# SensorIoTDisplay.net
KiCad netlist of a schematic drawn in EAGLE
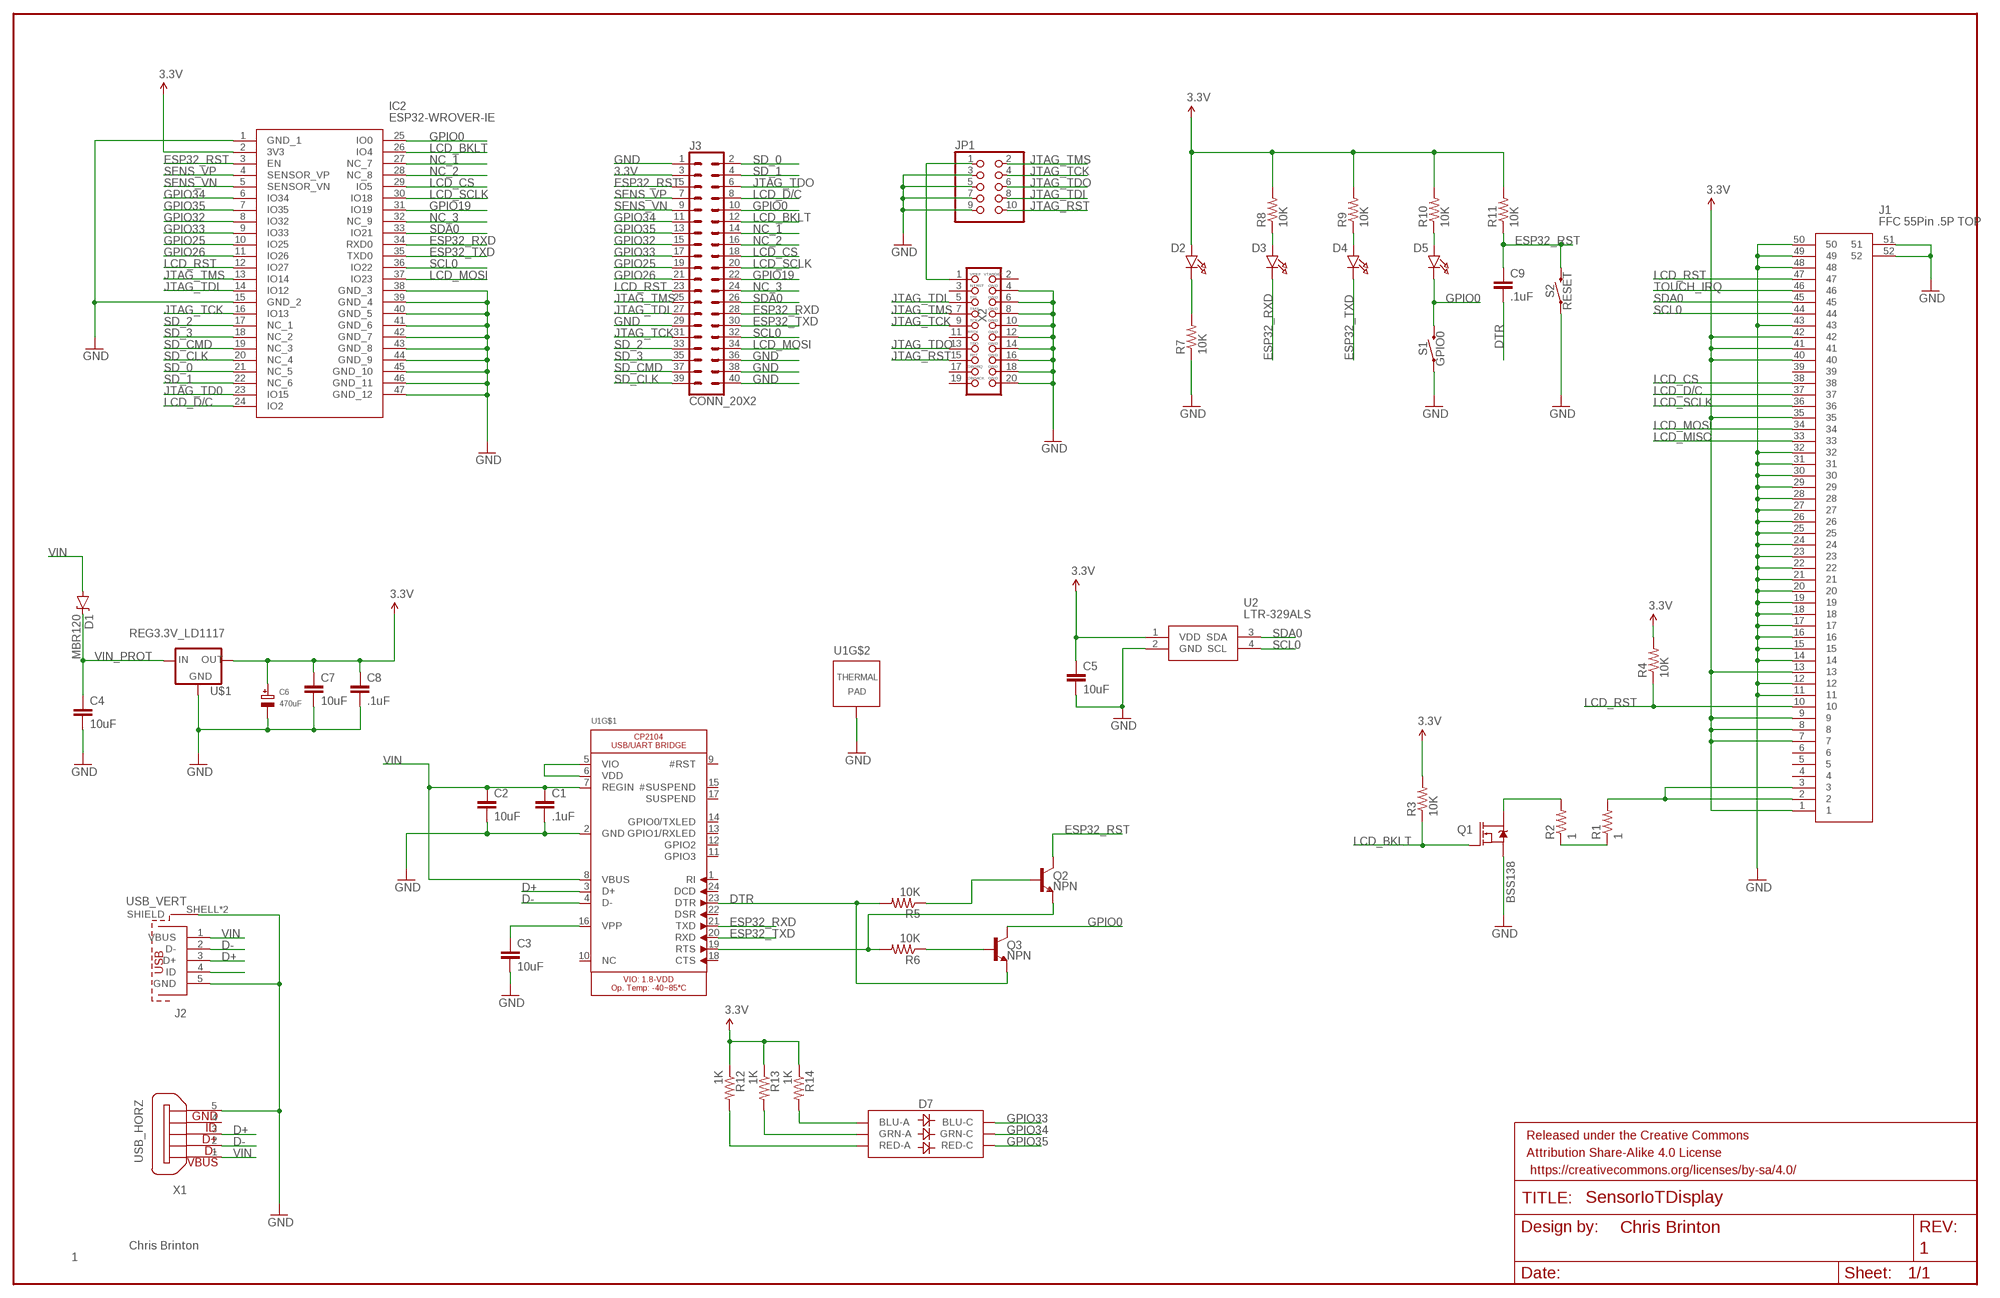
[diagram p0: schematic, sheet 1]

(export (version "E")
  (design (tool "Eeschema 10.0.6"))
  (components
    (comp (ref "C1")
      (value ".1uF")
      (footprint "eagle-import:0805")
      (libsource (lib "eagle-import") (part "CAP0805"))
    )
    (comp (ref "C2")
      (value "10uF")
      (footprint "eagle-import:0805")
      (libsource (lib "eagle-import") (part "CAP0805"))
    )
    (comp (ref "C3")
      (value "10uF")
      (footprint "eagle-import:0805")
      (libsource (lib "eagle-import") (part "CAP0805"))
    )
    (comp (ref "C4")
      (value "10uF")
      (footprint "eagle-import:0805")
      (libsource (lib "eagle-import") (part "CAP0805"))
    )
    (comp (ref "C5")
      (value "10uF")
      (footprint "eagle-import:0805")
      (libsource (lib "eagle-import") (part "CAP0805"))
    )
    (comp (ref "C6")
      (value "470uF")
      (footprint "eagle-import:EIA7343-31_D-R")
      (libsource (lib "eagle-import") (part "CAP_TANTALUMD/7343_REFLOW"))
    )
    (comp (ref "C7")
      (value "10uF")
      (footprint "eagle-import:0805")
      (libsource (lib "eagle-import") (part "CAP0805"))
    )
    (comp (ref "C8")
      (value ".1uF")
      (footprint "eagle-import:0805")
      (libsource (lib "eagle-import") (part "CAP0805"))
    )
    (comp (ref "C9")
      (value ".1uF")
      (footprint "eagle-import:0805")
      (libsource (lib "eagle-import") (part "CAP0805"))
    )
    (comp (ref "D1")
      (value "MBR120")
      (footprint "eagle-import:SOD-123")
      (libsource (lib "eagle-import") (part "DIODE-ZENER16V"))
    )
    (comp (ref "D2")
      (value "RED")
      (footprint "eagle-import:CHIPLED_0805_NOOUTLINE")
      (libsource (lib "eagle-import") (part "LED0805_NOOUTLINE"))
    )
    (comp (ref "D3")
      (value "GREEN")
      (footprint "eagle-import:CHIPLED_0805_NOOUTLINE")
      (libsource (lib "eagle-import") (part "LED0805_NOOUTLINE"))
    )
    (comp (ref "D4")
      (value "BLUE")
      (footprint "eagle-import:CHIPLED_0805_NOOUTLINE")
      (libsource (lib "eagle-import") (part "LED0805_NOOUTLINE"))
    )
    (comp (ref "D5")
      (value "BLUE")
      (footprint "eagle-import:CHIPLED_0805_NOOUTLINE")
      (libsource (lib "eagle-import") (part "LED0805_NOOUTLINE"))
    )
    (comp (ref "D7")
      (value "LED-RGBNO_IC")
      (footprint "eagle-import:LED-TRICOLOR-5050")
      (libsource (lib "eagle-import") (part "LED-RGBNO_IC"))
    )
    (comp (ref "FRAME1")
      (value "FRAME-LEDGER")
      (footprint "eagle-import:CREATIVE_COMMONS")
      (fields (field (name "DESIGNER") "Chris Brinton") (field (name "REV") "1"))
      (libsource (lib "eagle-import") (part "FRAME-LEDGER"))
    )
    (comp (ref "IC2")
      (value "ESP32-WROVER-IE")
      (footprint "eagle-import:ESP32WROVERIEM213EH6464UH3Q0")
      (fields
        (field (name "MANUFACTURER_PART_NUMBER") "ESP32-WROVER-IE(M213EH6464UH3Q0)")
        (field (name "MOUSER_PART_NUMBER") "356-ESP32WRVIE6464UC")
      )
      (libsource (lib "eagle-import") (part "ESP32-WROVER-IE_M213EH6464UH3Q"))
    )
    (comp (ref "J1")
      (value "FFC 55Pin .5P TOP")
      (footprint "eagle-import:FH12A50S05SH55")
      (fields
        (field (name "MANUFACTURER_PART_NUMBER") "FH12A-50S-0.5SH(55)")
        (field (name "MOUSER_PART_NUMBER") "798-FH12A-50S0.5SH55")
        (field (name "RS_PART_NUMBER") "6882833P")
      )
      (libsource (lib "eagle-import") (part "FH12A-50S-0.5SH_55_"))
    )
    (comp (ref "J2")
      (value "USB_VERT")
      (footprint "eagle-import:614105150621")
      (fields (field (name "MF") "Wurth Electronics") (field (name "MP") "614105150621"))
      (libsource (lib "eagle-import") (part "614105150621"))
    )
    (comp (ref "J3")
      (value "CONN_20X2")
      (footprint "eagle-import:2X20")
      (libsource (lib "eagle-import") (part "CONN_20X2"))
    )
    (comp (ref "JP1")
      (value "HEADER-2X51.27MM")
      (footprint "eagle-import:2X05_1.27MM_SMT")
      (libsource (lib "eagle-import") (part "HEADER-2X51.27MM"))
    )
    (comp (ref "Q1")
      (value "BSS138")
      (footprint "eagle-import:SOT23-3")
      (libsource (lib "eagle-import") (part "MOSFET-NCH-BSS138"))
    )
    (comp (ref "Q2")
      (value "NPN")
      (footprint "eagle-import:SOT23-3")
      (libsource (lib "eagle-import") (part "TRANS_NPN-MMBT2222AL"))
    )
    (comp (ref "Q3")
      (value "NPN")
      (footprint "eagle-import:SOT23-3")
      (libsource (lib "eagle-import") (part "TRANS_NPN-MMBT2222AL"))
    )
    (comp (ref "R1")
      (value "1")
      (footprint "eagle-import:0805")
      (libsource (lib "eagle-import") (part "RESISTOR0805-RES"))
    )
    (comp (ref "R2")
      (value "1")
      (footprint "eagle-import:0805")
      (libsource (lib "eagle-import") (part "RESISTOR0805-RES"))
    )
    (comp (ref "R3")
      (value "10K")
      (footprint "eagle-import:0805")
      (libsource (lib "eagle-import") (part "RESISTOR0805-RES"))
    )
    (comp (ref "R4")
      (value "10K")
      (footprint "eagle-import:0805")
      (libsource (lib "eagle-import") (part "RESISTOR0805-RES"))
    )
    (comp (ref "R5")
      (value "10K")
      (footprint "eagle-import:0805")
      (libsource (lib "eagle-import") (part "RESISTOR0805-RES"))
    )
    (comp (ref "R6")
      (value "10K")
      (footprint "eagle-import:0805")
      (libsource (lib "eagle-import") (part "RESISTOR0805-RES"))
    )
    (comp (ref "R7")
      (value "10K")
      (footprint "eagle-import:0805")
      (libsource (lib "eagle-import") (part "RESISTOR0805-RES"))
    )
    (comp (ref "R8")
      (value "10K")
      (footprint "eagle-import:0805")
      (libsource (lib "eagle-import") (part "RESISTOR0805-RES"))
    )
    (comp (ref "R9")
      (value "10K")
      (footprint "eagle-import:0805")
      (libsource (lib "eagle-import") (part "RESISTOR0805-RES"))
    )
    (comp (ref "R10")
      (value "10K")
      (footprint "eagle-import:0805")
      (libsource (lib "eagle-import") (part "RESISTOR0805-RES"))
    )
    (comp (ref "R11")
      (value "10K")
      (footprint "eagle-import:0805")
      (libsource (lib "eagle-import") (part "RESISTOR0805-RES"))
    )
    (comp (ref "R12")
      (value "1K")
      (footprint "eagle-import:0805")
      (libsource (lib "eagle-import") (part "RESISTOR0805-RES"))
    )
    (comp (ref "R13")
      (value "1K")
      (footprint "eagle-import:0805")
      (libsource (lib "eagle-import") (part "RESISTOR0805-RES"))
    )
    (comp (ref "R14")
      (value "1K")
      (footprint "eagle-import:0805")
      (libsource (lib "eagle-import") (part "RESISTOR0805-RES"))
    )
    (comp (ref "S1")
      (value "GPIO0")
      (footprint "eagle-import:TACTILE_SWITCH_SMD_4.6X2.8MM")
      (libsource (lib "eagle-import") (part "MOMENTARY-SWITCH-SPST-SMD-4.6X2.8MM"))
    )
    (comp (ref "S2")
      (value "RESET")
      (footprint "eagle-import:TACTILE_SWITCH_SMD_4.6X2.8MM")
      (libsource (lib "eagle-import") (part "MOMENTARY-SWITCH-SPST-SMD-4.6X2.8MM"))
    )
    (comp (ref "U$1")
      (value "REG3.3V_LD1117")
      (footprint "eagle-import:SOT223")
      (libsource (lib "eagle-import") (part "V_REG_LD1117VXXLD1117-SMD"))
    )
    (comp (ref "U1")
      (value "CP2104")
      (footprint "eagle-import:QFN24_4MM_SMSC")
      (libsource (lib "eagle-import") (part "CP2104"))
    )
    (comp (ref "U2")
      (value "LTR-329ALS")
      (footprint "eagle-import:LTR329ALS01")
      (fields
        (field (name "MANUFACTURER_PART_NUMBER") "LTR-329ALS-01")
        (field (name "MOUSER_PART_NUMBER") "859-LTR-329ALS-01")
      )
      (libsource (lib "eagle-import") (part "LTR-329ALS-01"))
    )
    (comp (ref "X1")
      (value "USB_HORZ")
      (footprint "eagle-import:ZX62D-B-5PA8")
      (fields (field (name "MF") "Hirose") (field (name "MPN") "ZX62D-B-5PA8"))
      (libsource (lib "eagle-import") (part "ZX62D-B-5PA8"))
    )
    (comp (ref "X2")
      (value "MICROBUILDER_JTAG-ARM7SMT_FEMALE")
      (footprint "eagle-import:MICROBUILDER_2X10_SMT_FEMALE")
      (libsource (lib "eagle-import") (part "MICROBUILDER_JTAG-ARM7SMT_FEMALE"))
    )
  )
  (nets
    (net (code "1") (name "/D+") (class "Default")
      (node (ref "J2") (pin "3") (pinfunction "D+_3") (pintype "passive"))
      (node (ref "U1") (pin "3") (pinfunction "D+_3") (pintype "bidirectional"))
      (node (ref "X1") (pin "3") (pinfunction "3_3") (pintype "passive"))
    )
    (net (code "2") (name "/D-") (class "Default")
      (node (ref "J2") (pin "2") (pinfunction "D-_2") (pintype "passive"))
      (node (ref "U1") (pin "4") (pinfunction "D-_4") (pintype "bidirectional"))
      (node (ref "X1") (pin "2") (pinfunction "2_2") (pintype "passive"))
    )
    (net (code "3") (name "/DTR") (class "Default")
      (node (ref "C9") (pin "2") (pinfunction "2_2") (pintype "passive"))
      (node (ref "Q3") (pin "2") (pinfunction "E_2") (pintype "passive"))
      (node (ref "R5") (pin "2") (pinfunction "2_2") (pintype "passive"))
      (node (ref "U1") (pin "23") (pinfunction "DTR_23") (pintype "output"))
    )
    (net (code "4") (name "/ESP32_RST") (class "Default")
      (node (ref "C9") (pin "1") (pinfunction "1_1") (pintype "passive"))
      (node (ref "IC2") (pin "3") (pinfunction "EN_3") (pintype "bidirectional"))
      (node (ref "J3") (pin "5") (pinfunction "5_5") (pintype "passive"))
      (node (ref "Q2") (pin "3") (pinfunction "C_3") (pintype "passive"))
      (node (ref "R11") (pin "1") (pinfunction "1_1") (pintype "passive"))
      (node (ref "S2") (pin "3") (pinfunction "2_3") (pintype "passive"))
      (node (ref "S2") (pin "4") (pinfunction "2_4") (pintype "passive"))
    )
    (net (code "5") (name "/ESP32_RXD") (class "Default")
      (node (ref "D3") (pin "C") (pinfunction "C_C") (pintype "passive"))
      (node (ref "IC2") (pin "34") (pinfunction "RXD0_34") (pintype "bidirectional"))
      (node (ref "J3") (pin "28") (pinfunction "28_28") (pintype "passive"))
      (node (ref "U1") (pin "21") (pinfunction "TXD_21") (pintype "output"))
    )
    (net (code "6") (name "/ESP32_TXD") (class "Default")
      (node (ref "D4") (pin "C") (pinfunction "C_C") (pintype "passive"))
      (node (ref "IC2") (pin "35") (pinfunction "TXD0_35") (pintype "bidirectional"))
      (node (ref "J3") (pin "30") (pinfunction "30_30") (pintype "passive"))
      (node (ref "U1") (pin "20") (pinfunction "RXD_20") (pintype "input"))
    )
    (net (code "7") (name "/GPIO0") (class "Default")
      (node (ref "D5") (pin "C") (pinfunction "C_C") (pintype "passive"))
      (node (ref "IC2") (pin "25") (pinfunction "IO0_25") (pintype "bidirectional"))
      (node (ref "J3") (pin "10") (pinfunction "10_10") (pintype "passive"))
      (node (ref "Q3") (pin "3") (pinfunction "C_3") (pintype "passive"))
      (node (ref "S1") (pin "3") (pinfunction "2_3") (pintype "passive"))
      (node (ref "S1") (pin "4") (pinfunction "2_4") (pintype "passive"))
    )
    (net (code "8") (name "/GPIO19") (class "Default")
      (node (ref "IC2") (pin "31") (pinfunction "IO19_31") (pintype "bidirectional"))
      (node (ref "J3") (pin "22") (pinfunction "22_22") (pintype "passive"))
    )
    (net (code "9") (name "/GPIO25") (class "Default")
      (node (ref "IC2") (pin "10") (pinfunction "IO25_10") (pintype "bidirectional"))
      (node (ref "J3") (pin "19") (pinfunction "19_19") (pintype "passive"))
    )
    (net (code "10") (name "/GPIO26") (class "Default")
      (node (ref "IC2") (pin "11") (pinfunction "IO26_11") (pintype "bidirectional"))
      (node (ref "J3") (pin "21") (pinfunction "21_21") (pintype "passive"))
    )
    (net (code "11") (name "/GPIO32") (class "Default")
      (node (ref "IC2") (pin "8") (pinfunction "IO32_8") (pintype "bidirectional"))
      (node (ref "J3") (pin "15") (pinfunction "15_15") (pintype "passive"))
    )
    (net (code "12") (name "/GPIO33") (class "Default")
      (node (ref "D7") (pin "4") (pinfunction "BLU-C_4") (pintype "bidirectional"))
      (node (ref "IC2") (pin "9") (pinfunction "IO33_9") (pintype "bidirectional"))
      (node (ref "J3") (pin "17") (pinfunction "17_17") (pintype "passive"))
    )
    (net (code "13") (name "/GPIO34") (class "Default")
      (node (ref "D7") (pin "6") (pinfunction "GRN-C_6") (pintype "bidirectional"))
      (node (ref "IC2") (pin "6") (pinfunction "IO34_6") (pintype "bidirectional"))
      (node (ref "J3") (pin "11") (pinfunction "11_11") (pintype "passive"))
    )
    (net (code "14") (name "/GPIO35") (class "Default")
      (node (ref "D7") (pin "5") (pinfunction "RED-C_5") (pintype "bidirectional"))
      (node (ref "IC2") (pin "7") (pinfunction "IO35_7") (pintype "bidirectional"))
      (node (ref "J3") (pin "13") (pinfunction "13_13") (pintype "passive"))
    )
    (net (code "15") (name "/JTAG_RST") (class "Default")
      (node (ref "JP1") (pin "10") (pinfunction "10_10") (pintype "passive"))
      (node (ref "X2") (pin "15") (pinfunction "15_15") (pintype "passive"))
    )
    (net (code "16") (name "/JTAG_TCK") (class "Default")
      (node (ref "IC2") (pin "16") (pinfunction "IO13_16") (pintype "bidirectional"))
      (node (ref "J3") (pin "31") (pinfunction "31_31") (pintype "passive"))
      (node (ref "JP1") (pin "4") (pinfunction "4_4") (pintype "passive"))
      (node (ref "X2") (pin "9") (pinfunction "9_9") (pintype "passive"))
    )
    (net (code "17") (name "/JTAG_TD0") (class "Default")
      (node (ref "IC2") (pin "23") (pinfunction "IO15_23") (pintype "bidirectional"))
    )
    (net (code "18") (name "/JTAG_TDI") (class "Default")
      (node (ref "IC2") (pin "14") (pinfunction "IO12_14") (pintype "bidirectional"))
      (node (ref "J3") (pin "27") (pinfunction "27_27") (pintype "passive"))
      (node (ref "JP1") (pin "8") (pinfunction "8_8") (pintype "passive"))
      (node (ref "X2") (pin "5") (pinfunction "5_5") (pintype "passive"))
    )
    (net (code "19") (name "/JTAG_TDO") (class "Default")
      (node (ref "J3") (pin "6") (pinfunction "6_6") (pintype "passive"))
      (node (ref "JP1") (pin "6") (pinfunction "6_6") (pintype "passive"))
      (node (ref "X2") (pin "13") (pinfunction "13_13") (pintype "passive"))
    )
    (net (code "20") (name "/JTAG_TMS") (class "Default")
      (node (ref "IC2") (pin "13") (pinfunction "IO14_13") (pintype "bidirectional"))
      (node (ref "J3") (pin "25") (pinfunction "25_25") (pintype "passive"))
      (node (ref "JP1") (pin "2") (pinfunction "2_2") (pintype "passive"))
      (node (ref "X2") (pin "7") (pinfunction "7_7") (pintype "passive"))
    )
    (net (code "21") (name "/LCD_BKLT") (class "Default")
      (node (ref "IC2") (pin "26") (pinfunction "IO4_26") (pintype "bidirectional"))
      (node (ref "J3") (pin "12") (pinfunction "12_12") (pintype "passive"))
      (node (ref "Q1") (pin "1") (pinfunction "G_1") (pintype "bidirectional"))
      (node (ref "R3") (pin "1") (pinfunction "1_1") (pintype "passive"))
    )
    (net (code "22") (name "/LCD_CS") (class "Default")
      (node (ref "IC2") (pin "29") (pinfunction "IO5_29") (pintype "bidirectional"))
      (node (ref "J1") (pin "38") (pinfunction "38_38") (pintype "bidirectional"))
      (node (ref "J3") (pin "18") (pinfunction "18_18") (pintype "passive"))
    )
    (net (code "23") (name "/LCD_D{slash}C") (class "Default")
      (node (ref "IC2") (pin "24") (pinfunction "IO2_24") (pintype "bidirectional"))
      (node (ref "J1") (pin "37") (pinfunction "37_37") (pintype "bidirectional"))
      (node (ref "J3") (pin "8") (pinfunction "8_8") (pintype "passive"))
    )
    (net (code "24") (name "/LCD_MISO") (class "Default")
      (node (ref "J1") (pin "33") (pinfunction "33_33") (pintype "bidirectional"))
    )
    (net (code "25") (name "/LCD_MOSI") (class "Default")
      (node (ref "IC2") (pin "37") (pinfunction "IO23_37") (pintype "bidirectional"))
      (node (ref "J1") (pin "34") (pinfunction "34_34") (pintype "bidirectional"))
      (node (ref "J3") (pin "34") (pinfunction "34_34") (pintype "passive"))
    )
    (net (code "26") (name "/LCD_RST") (class "Default")
      (node (ref "IC2") (pin "12") (pinfunction "IO27_12") (pintype "bidirectional"))
      (node (ref "J1") (pin "10") (pinfunction "10_10") (pintype "bidirectional"))
      (node (ref "J1") (pin "47") (pinfunction "47_47") (pintype "bidirectional"))
      (node (ref "J3") (pin "23") (pinfunction "23_23") (pintype "passive"))
      (node (ref "R4") (pin "1") (pinfunction "1_1") (pintype "passive"))
    )
    (net (code "27") (name "/LCD_SCLK") (class "Default")
      (node (ref "IC2") (pin "30") (pinfunction "IO18_30") (pintype "bidirectional"))
      (node (ref "J1") (pin "36") (pinfunction "36_36") (pintype "bidirectional"))
      (node (ref "J3") (pin "20") (pinfunction "20_20") (pintype "passive"))
    )
    (net (code "28") (name "/NC_1") (class "Default")
      (node (ref "IC2") (pin "27") (pinfunction "NC_7_27") (pintype "bidirectional"))
      (node (ref "J3") (pin "14") (pinfunction "14_14") (pintype "passive"))
    )
    (net (code "29") (name "/NC_2") (class "Default")
      (node (ref "IC2") (pin "28") (pinfunction "NC_8_28") (pintype "bidirectional"))
      (node (ref "J3") (pin "16") (pinfunction "16_16") (pintype "passive"))
    )
    (net (code "30") (name "/NC_3") (class "Default")
      (node (ref "IC2") (pin "32") (pinfunction "NC_9_32") (pintype "bidirectional"))
      (node (ref "J3") (pin "24") (pinfunction "24_24") (pintype "passive"))
    )
    (net (code "31") (name "/SCL0") (class "Default")
      (node (ref "IC2") (pin "36") (pinfunction "IO22_36") (pintype "bidirectional"))
      (node (ref "J1") (pin "44") (pinfunction "44_44") (pintype "bidirectional"))
      (node (ref "J3") (pin "32") (pinfunction "32_32") (pintype "passive"))
      (node (ref "U2") (pin "4") (pinfunction "SCL_4") (pintype "bidirectional"))
    )
    (net (code "32") (name "/SDA0") (class "Default")
      (node (ref "IC2") (pin "33") (pinfunction "IO21_33") (pintype "bidirectional"))
      (node (ref "J1") (pin "45") (pinfunction "45_45") (pintype "bidirectional"))
      (node (ref "J3") (pin "26") (pinfunction "26_26") (pintype "passive"))
      (node (ref "U2") (pin "3") (pinfunction "SDA_3") (pintype "bidirectional"))
    )
    (net (code "33") (name "/SD_0") (class "Default")
      (node (ref "IC2") (pin "21") (pinfunction "NC_5_21") (pintype "bidirectional"))
      (node (ref "J3") (pin "2") (pinfunction "2_2") (pintype "passive"))
    )
    (net (code "34") (name "/SD_1") (class "Default")
      (node (ref "IC2") (pin "22") (pinfunction "NC_6_22") (pintype "bidirectional"))
      (node (ref "J3") (pin "4") (pinfunction "4_4") (pintype "passive"))
    )
    (net (code "35") (name "/SD_2") (class "Default")
      (node (ref "IC2") (pin "17") (pinfunction "NC_1_17") (pintype "bidirectional"))
      (node (ref "J3") (pin "33") (pinfunction "33_33") (pintype "passive"))
    )
    (net (code "36") (name "/SD_3") (class "Default")
      (node (ref "IC2") (pin "18") (pinfunction "NC_2_18") (pintype "bidirectional"))
      (node (ref "J3") (pin "35") (pinfunction "35_35") (pintype "passive"))
    )
    (net (code "37") (name "/SD_CLK") (class "Default")
      (node (ref "IC2") (pin "20") (pinfunction "NC_4_20") (pintype "bidirectional"))
      (node (ref "J3") (pin "39") (pinfunction "39_39") (pintype "passive"))
    )
    (net (code "38") (name "/SD_CMD") (class "Default")
      (node (ref "IC2") (pin "19") (pinfunction "NC_3_19") (pintype "bidirectional"))
      (node (ref "J3") (pin "37") (pinfunction "37_37") (pintype "passive"))
    )
    (net (code "39") (name "/SENS_VN") (class "Default")
      (node (ref "IC2") (pin "5") (pinfunction "SENSOR_VN_5") (pintype "bidirectional"))
      (node (ref "J3") (pin "9") (pinfunction "9_9") (pintype "passive"))
    )
    (net (code "40") (name "/SENS_VP") (class "Default")
      (node (ref "IC2") (pin "4") (pinfunction "SENSOR_VP_4") (pintype "bidirectional"))
      (node (ref "J3") (pin "7") (pinfunction "7_7") (pintype "passive"))
    )
    (net (code "41") (name "/TOUCH_IRQ") (class "Default")
      (node (ref "J1") (pin "46") (pinfunction "46_46") (pintype "bidirectional"))
    )
    (net (code "42") (name "/VIN") (class "Default")
      (node (ref "C1") (pin "1") (pinfunction "1_1") (pintype "passive"))
      (node (ref "C2") (pin "1") (pinfunction "1_1") (pintype "passive"))
      (node (ref "D1") (pin "A") (pinfunction "A_A") (pintype "passive"))
      (node (ref "J2") (pin "1") (pinfunction "VBUS_1") (pintype "passive"))
      (node (ref "U1") (pin "7") (pinfunction "REGIN_7") (pintype "power_in"))
      (node (ref "U1") (pin "8") (pinfunction "VBUS_8") (pintype "power_in"))
      (node (ref "X1") (pin "1") (pinfunction "1_1") (pintype "passive"))
    )
    (net (code "43") (name "/VIN_PROT") (class "Default")
      (node (ref "C4") (pin "1") (pinfunction "1_1") (pintype "passive"))
      (node (ref "D1") (pin "C") (pinfunction "C_C") (pintype "passive"))
      (node (ref "U$1") (pin "3") (pinfunction "IN_3") (pintype "input"))
    )
    (net (code "44") (name "3.3V") (class "Default")
      (node (ref "C5") (pin "1") (pinfunction "1_1") (pintype "passive"))
      (node (ref "C6") (pin "+") (pinfunction "+_+") (pintype "passive"))
      (node (ref "C7") (pin "1") (pinfunction "1_1") (pintype "passive"))
      (node (ref "C8") (pin "1") (pinfunction "1_1") (pintype "passive"))
      (node (ref "D2") (pin "A") (pinfunction "A_A") (pintype "passive"))
      (node (ref "IC2") (pin "2") (pinfunction "3V3_2") (pintype "bidirectional"))
      (node (ref "J1") (pin "1") (pinfunction "1_1") (pintype "bidirectional"))
      (node (ref "J1") (pin "13") (pinfunction "13_13") (pintype "bidirectional"))
      (node (ref "J1") (pin "35") (pinfunction "35_35") (pintype "bidirectional"))
      (node (ref "J1") (pin "40") (pinfunction "40_40") (pintype "bidirectional"))
      (node (ref "J1") (pin "41") (pinfunction "41_41") (pintype "bidirectional"))
      (node (ref "J1") (pin "42") (pinfunction "42_42") (pintype "bidirectional"))
      (node (ref "J1") (pin "7") (pinfunction "7_7") (pintype "bidirectional"))
      (node (ref "J1") (pin "8") (pinfunction "8_8") (pintype "bidirectional"))
      (node (ref "J1") (pin "9") (pinfunction "9_9") (pintype "bidirectional"))
      (node (ref "J3") (pin "3") (pinfunction "3_3") (pintype "passive"))
      (node (ref "R10") (pin "2") (pinfunction "2_2") (pintype "passive"))
      (node (ref "R11") (pin "2") (pinfunction "2_2") (pintype "passive"))
      (node (ref "R12") (pin "1") (pinfunction "1_1") (pintype "passive"))
      (node (ref "R13") (pin "1") (pinfunction "1_1") (pintype "passive"))
      (node (ref "R14") (pin "1") (pinfunction "1_1") (pintype "passive"))
      (node (ref "R3") (pin "2") (pinfunction "2_2") (pintype "passive"))
      (node (ref "R4") (pin "2") (pinfunction "2_2") (pintype "passive"))
      (node (ref "R8") (pin "2") (pinfunction "2_2") (pintype "passive"))
      (node (ref "R9") (pin "2") (pinfunction "2_2") (pintype "passive"))
      (node (ref "U$1") (pin "2") (pinfunction "OUT_2") (pintype "passive"))
      (node (ref "U2") (pin "1") (pinfunction "VDD_1") (pintype "bidirectional"))
    )
    (net (code "45") (name "GND") (class "Default")
      (node (ref "C1") (pin "2") (pinfunction "2_2") (pintype "passive"))
      (node (ref "C2") (pin "2") (pinfunction "2_2") (pintype "passive"))
      (node (ref "C3") (pin "2") (pinfunction "2_2") (pintype "passive"))
      (node (ref "C4") (pin "2") (pinfunction "2_2") (pintype "passive"))
      (node (ref "C5") (pin "2") (pinfunction "2_2") (pintype "passive"))
      (node (ref "C6") (pin "-") (pinfunction "-_-") (pintype "passive"))
      (node (ref "C7") (pin "2") (pinfunction "2_2") (pintype "passive"))
      (node (ref "C8") (pin "2") (pinfunction "2_2") (pintype "passive"))
      (node (ref "IC2") (pin "1") (pinfunction "GND_1_1") (pintype "bidirectional"))
      (node (ref "IC2") (pin "15") (pinfunction "GND_2_15") (pintype "bidirectional"))
      (node (ref "IC2") (pin "38") (pinfunction "GND_3_38") (pintype "bidirectional"))
      (node (ref "IC2") (pin "39") (pinfunction "GND_4_39") (pintype "bidirectional"))
      (node (ref "IC2") (pin "40") (pinfunction "GND_5_40") (pintype "bidirectional"))
      (node (ref "IC2") (pin "41") (pinfunction "GND_6_41") (pintype "bidirectional"))
      (node (ref "IC2") (pin "42") (pinfunction "GND_7_42") (pintype "bidirectional"))
      (node (ref "IC2") (pin "43") (pinfunction "GND_8_43") (pintype "bidirectional"))
      (node (ref "IC2") (pin "44") (pinfunction "GND_9_44") (pintype "bidirectional"))
      (node (ref "IC2") (pin "45") (pinfunction "GND_10_45") (pintype "bidirectional"))
      (node (ref "IC2") (pin "46") (pinfunction "GND_11_46") (pintype "bidirectional"))
      (node (ref "IC2") (pin "47") (pinfunction "GND_12_47") (pintype "bidirectional"))
      (node (ref "J1") (pin "11") (pinfunction "11_11") (pintype "bidirectional"))
      (node (ref "J1") (pin "12") (pinfunction "12_12") (pintype "bidirectional"))
      (node (ref "J1") (pin "14") (pinfunction "14_14") (pintype "bidirectional"))
      (node (ref "J1") (pin "15") (pinfunction "15_15") (pintype "bidirectional"))
      (node (ref "J1") (pin "16") (pinfunction "16_16") (pintype "bidirectional"))
      (node (ref "J1") (pin "17") (pinfunction "17_17") (pintype "bidirectional"))
      (node (ref "J1") (pin "18") (pinfunction "18_18") (pintype "bidirectional"))
      (node (ref "J1") (pin "19") (pinfunction "19_19") (pintype "bidirectional"))
      (node (ref "J1") (pin "20") (pinfunction "20_20") (pintype "bidirectional"))
      (node (ref "J1") (pin "21") (pinfunction "21_21") (pintype "bidirectional"))
      (node (ref "J1") (pin "22") (pinfunction "22_22") (pintype "bidirectional"))
      (node (ref "J1") (pin "23") (pinfunction "23_23") (pintype "bidirectional"))
      (node (ref "J1") (pin "24") (pinfunction "24_24") (pintype "bidirectional"))
      (node (ref "J1") (pin "25") (pinfunction "25_25") (pintype "bidirectional"))
      (node (ref "J1") (pin "26") (pinfunction "26_26") (pintype "bidirectional"))
      (node (ref "J1") (pin "27") (pinfunction "27_27") (pintype "bidirectional"))
      (node (ref "J1") (pin "28") (pinfunction "28_28") (pintype "bidirectional"))
      (node (ref "J1") (pin "29") (pinfunction "29_29") (pintype "bidirectional"))
      (node (ref "J1") (pin "30") (pinfunction "30_30") (pintype "bidirectional"))
      (node (ref "J1") (pin "31") (pinfunction "31_31") (pintype "bidirectional"))
      (node (ref "J1") (pin "32") (pinfunction "32_32") (pintype "bidirectional"))
      (node (ref "J1") (pin "43") (pinfunction "43_43") (pintype "bidirectional"))
      (node (ref "J1") (pin "48") (pinfunction "48_48") (pintype "bidirectional"))
      (node (ref "J1") (pin "49") (pinfunction "49_49") (pintype "bidirectional"))
      (node (ref "J1") (pin "50") (pinfunction "50_50") (pintype "bidirectional"))
      (node (ref "J1") (pin "51") (pinfunction "51_51") (pintype "bidirectional"))
      (node (ref "J1") (pin "52") (pinfunction "52_52") (pintype "bidirectional"))
      (node (ref "J2") (pin "5") (pinfunction "GND_5") (pintype "passive"))
      (node (ref "J2") (pin "SHELL") (pinfunction "SHIELD_SHELL") (pintype "passive"))
      (node (ref "J2") (pin "SHELL1") (pinfunction "SHIELD_SHELL1") (pintype "passive"))
      (node (ref "J3") (pin "1") (pinfunction "1_1") (pintype "passive"))
      (node (ref "J3") (pin "29") (pinfunction "29_29") (pintype "passive"))
      (node (ref "J3") (pin "36") (pinfunction "36_36") (pintype "passive"))
      (node (ref "J3") (pin "38") (pinfunction "38_38") (pintype "passive"))
      (node (ref "J3") (pin "40") (pinfunction "40_40") (pintype "passive"))
      (node (ref "JP1") (pin "3") (pinfunction "3_3") (pintype "passive"))
      (node (ref "JP1") (pin "5") (pinfunction "5_5") (pintype "passive"))
      (node (ref "JP1") (pin "7") (pinfunction "7_7") (pintype "passive"))
      (node (ref "JP1") (pin "9") (pinfunction "9_9") (pintype "passive"))
      (node (ref "Q1") (pin "2") (pinfunction "S_2") (pintype "bidirectional"))
      (node (ref "R7") (pin "1") (pinfunction "1_1") (pintype "passive"))
      (node (ref "S1") (pin "1") (pinfunction "1_1") (pintype "passive"))
      (node (ref "S1") (pin "2") (pinfunction "1_2") (pintype "passive"))
      (node (ref "S2") (pin "1") (pinfunction "1_1") (pintype "passive"))
      (node (ref "S2") (pin "2") (pinfunction "1_2") (pintype "passive"))
      (node (ref "U$1") (pin "1") (pinfunction "GND_1") (pintype "input"))
      (node (ref "U1") (pin "2") (pinfunction "GND_2") (pintype "power_in"))
      (node (ref "U1") (pin "THERM") (pinfunction "TP_THERM") (pintype "power_in"))
      (node (ref "U2") (pin "2") (pinfunction "GND_2") (pintype "bidirectional"))
      (node (ref "X1") (pin "5") (pinfunction "5_5") (pintype "passive"))
      (node (ref "X2") (pin "10") (pinfunction "10_10") (pintype "passive"))
      (node (ref "X2") (pin "12") (pinfunction "12_12") (pintype "passive"))
      (node (ref "X2") (pin "14") (pinfunction "14_14") (pintype "passive"))
      (node (ref "X2") (pin "16") (pinfunction "16_16") (pintype "passive"))
      (node (ref "X2") (pin "18") (pinfunction "18_18") (pintype "passive"))
      (node (ref "X2") (pin "20") (pinfunction "20_20") (pintype "passive"))
      (node (ref "X2") (pin "4") (pinfunction "4_4") (pintype "passive"))
      (node (ref "X2") (pin "6") (pinfunction "6_6") (pintype "passive"))
      (node (ref "X2") (pin "8") (pinfunction "8_8") (pintype "passive"))
    )
    (net (code "46") (name "Net-(D2-PadC)") (class "Default")
      (node (ref "D2") (pin "C") (pinfunction "C_C") (pintype "passive"))
      (node (ref "R7") (pin "2") (pinfunction "2_2") (pintype "passive"))
    )
    (net (code "47") (name "Net-(D3-PadA)") (class "Default")
      (node (ref "D3") (pin "A") (pinfunction "A_A") (pintype "passive"))
      (node (ref "R8") (pin "1") (pinfunction "1_1") (pintype "passive"))
    )
    (net (code "48") (name "Net-(D4-PadA)") (class "Default")
      (node (ref "D4") (pin "A") (pinfunction "A_A") (pintype "passive"))
      (node (ref "R9") (pin "1") (pinfunction "1_1") (pintype "passive"))
    )
    (net (code "49") (name "Net-(D5-PadA)") (class "Default")
      (node (ref "D5") (pin "A") (pinfunction "A_A") (pintype "passive"))
      (node (ref "R10") (pin "1") (pinfunction "1_1") (pintype "passive"))
    )
    (net (code "50") (name "Net-(D7-BLU-A)") (class "Default")
      (node (ref "D7") (pin "3") (pinfunction "BLU-A_3") (pintype "bidirectional"))
      (node (ref "R14") (pin "2") (pinfunction "2_2") (pintype "passive"))
    )
    (net (code "51") (name "Net-(D7-GRN-A)") (class "Default")
      (node (ref "D7") (pin "1") (pinfunction "GRN-A_1") (pintype "bidirectional"))
      (node (ref "R13") (pin "2") (pinfunction "2_2") (pintype "passive"))
    )
    (net (code "52") (name "Net-(D7-RED-A)") (class "Default")
      (node (ref "D7") (pin "2") (pinfunction "RED-A_2") (pintype "bidirectional"))
      (node (ref "R12") (pin "2") (pinfunction "2_2") (pintype "passive"))
    )
    (net (code "53") (name "Net-(J1-Pad2)") (class "Default")
      (node (ref "J1") (pin "2") (pinfunction "2_2") (pintype "bidirectional"))
      (node (ref "J1") (pin "3") (pinfunction "3_3") (pintype "bidirectional"))
      (node (ref "R1") (pin "2") (pinfunction "2_2") (pintype "passive"))
    )
    (net (code "54") (name "Net-(JP1-Pad1)") (class "Default")
      (node (ref "JP1") (pin "1") (pinfunction "1_1") (pintype "passive"))
      (node (ref "X2") (pin "1") (pinfunction "1_1") (pintype "passive"))
    )
    (net (code "55") (name "Net-(Q1-D)") (class "Default")
      (node (ref "Q1") (pin "3") (pinfunction "D_3") (pintype "bidirectional"))
      (node (ref "R2") (pin "2") (pinfunction "2_2") (pintype "passive"))
    )
    (net (code "56") (name "Net-(Q2-B)") (class "Default")
      (node (ref "Q2") (pin "1") (pinfunction "B_1") (pintype "passive"))
      (node (ref "R5") (pin "1") (pinfunction "1_1") (pintype "passive"))
    )
    (net (code "57") (name "Net-(Q2-E)") (class "Default")
      (node (ref "Q2") (pin "2") (pinfunction "E_2") (pintype "passive"))
      (node (ref "R6") (pin "2") (pinfunction "2_2") (pintype "passive"))
      (node (ref "U1") (pin "19") (pinfunction "RTS_19") (pintype "output"))
    )
    (net (code "58") (name "Net-(Q3-B)") (class "Default")
      (node (ref "Q3") (pin "1") (pinfunction "B_1") (pintype "passive"))
      (node (ref "R6") (pin "1") (pinfunction "1_1") (pintype "passive"))
    )
    (net (code "59") (name "Net-(R1-Pad1)") (class "Default")
      (node (ref "R1") (pin "1") (pinfunction "1_1") (pintype "passive"))
      (node (ref "R2") (pin "1") (pinfunction "1_1") (pintype "passive"))
    )
    (net (code "60") (name "Net-(U1A-VDD)") (class "Default")
      (node (ref "U1") (pin "5") (pinfunction "VIO_5") (pintype "power_in"))
      (node (ref "U1") (pin "6") (pinfunction "VDD_6") (pintype "power_in"))
    )
    (net (code "61") (name "Net-(U1A-VPP)") (class "Default")
      (node (ref "C3") (pin "1") (pinfunction "1_1") (pintype "passive"))
      (node (ref "U1") (pin "16") (pinfunction "VPP_16") (pintype "bidirectional"))
    )
    (net (code "62") (name "unconnected-(J1-Pad4)") (class "Default")
      (node (ref "J1") (pin "4") (pinfunction "4_4") (pintype "bidirectional"))
    )
    (net (code "63") (name "unconnected-(J1-Pad5)") (class "Default")
      (node (ref "J1") (pin "5") (pinfunction "5_5") (pintype "bidirectional"))
    )
    (net (code "64") (name "unconnected-(J1-Pad6)") (class "Default")
      (node (ref "J1") (pin "6") (pinfunction "6_6") (pintype "bidirectional"))
    )
    (net (code "65") (name "unconnected-(J1-Pad39)") (class "Default")
      (node (ref "J1") (pin "39") (pinfunction "39_39") (pintype "bidirectional"))
    )
    (net (code "66") (name "unconnected-(J2-ID-Pad4)") (class "Default")
      (node (ref "J2") (pin "4") (pinfunction "ID_4") (pintype "passive"))
    )
    (net (code "67") (name "unconnected-(U1A-#RST-Pad9)") (class "Default")
      (node (ref "U1") (pin "9") (pinfunction "#RST_9") (pintype "bidirectional"))
    )
    (net (code "68") (name "unconnected-(U1A-#SUSPEND-Pad15)") (class "Default")
      (node (ref "U1") (pin "15") (pinfunction "#SUSPEND_15") (pintype "output"))
    )
    (net (code "69") (name "unconnected-(U1A-CTS-Pad18)") (class "Default")
      (node (ref "U1") (pin "18") (pinfunction "CTS_18") (pintype "input"))
    )
    (net (code "70") (name "unconnected-(U1A-DCD-Pad24)") (class "Default")
      (node (ref "U1") (pin "24") (pinfunction "DCD_24") (pintype "input"))
    )
    (net (code "71") (name "unconnected-(U1A-DSR-Pad22)") (class "Default")
      (node (ref "U1") (pin "22") (pinfunction "DSR_22") (pintype "input"))
    )
    (net (code "72") (name "unconnected-(U1A-GPIO0{slash}TXLED-Pad14)") (class "Default")
      (node (ref "U1") (pin "14") (pinfunction "GPIO0/TXLED_14") (pintype "bidirectional"))
    )
    (net (code "73") (name "unconnected-(U1A-GPIO1{slash}RXLED-Pad13)") (class "Default")
      (node (ref "U1") (pin "13") (pinfunction "GPIO1/RXLED_13") (pintype "bidirectional"))
    )
    (net (code "74") (name "unconnected-(U1A-GPIO2-Pad12)") (class "Default")
      (node (ref "U1") (pin "12") (pinfunction "GPIO2_12") (pintype "bidirectional"))
    )
    (net (code "75") (name "unconnected-(U1A-GPIO3-Pad11)") (class "Default")
      (node (ref "U1") (pin "11") (pinfunction "GPIO3_11") (pintype "bidirectional"))
    )
    (net (code "76") (name "unconnected-(U1A-NC-Pad10)") (class "Default")
      (node (ref "U1") (pin "10") (pinfunction "NC_10") (pintype "no_connect"))
    )
    (net (code "77") (name "unconnected-(U1A-RI-Pad1)") (class "Default")
      (node (ref "U1") (pin "1") (pinfunction "RI_1") (pintype "input"))
    )
    (net (code "78") (name "unconnected-(U1A-SUSPEND-Pad17)") (class "Default")
      (node (ref "U1") (pin "17") (pinfunction "SUSPEND_17") (pintype "output"))
    )
    (net (code "79") (name "unconnected-(X1-Pad4)") (class "Default")
      (node (ref "X1") (pin "4") (pinfunction "4_4") (pintype "passive"))
    )
    (net (code "80") (name "unconnected-(X2-Pad2)") (class "Default")
      (node (ref "X2") (pin "2") (pinfunction "2_2") (pintype "passive"))
    )
    (net (code "81") (name "unconnected-(X2-Pad3)") (class "Default")
      (node (ref "X2") (pin "3") (pinfunction "3_3") (pintype "passive"))
    )
    (net (code "82") (name "unconnected-(X2-Pad11)") (class "Default")
      (node (ref "X2") (pin "11") (pinfunction "11_11") (pintype "passive"))
    )
    (net (code "83") (name "unconnected-(X2-Pad17)") (class "Default")
      (node (ref "X2") (pin "17") (pinfunction "17_17") (pintype "passive"))
    )
    (net (code "84") (name "unconnected-(X2-Pad19)") (class "Default")
      (node (ref "X2") (pin "19") (pinfunction "19_19") (pintype "passive"))
    )
  )
)
